# Fan_control_design_v2.net
KiCad netlist of a schematic drawn in EAGLE
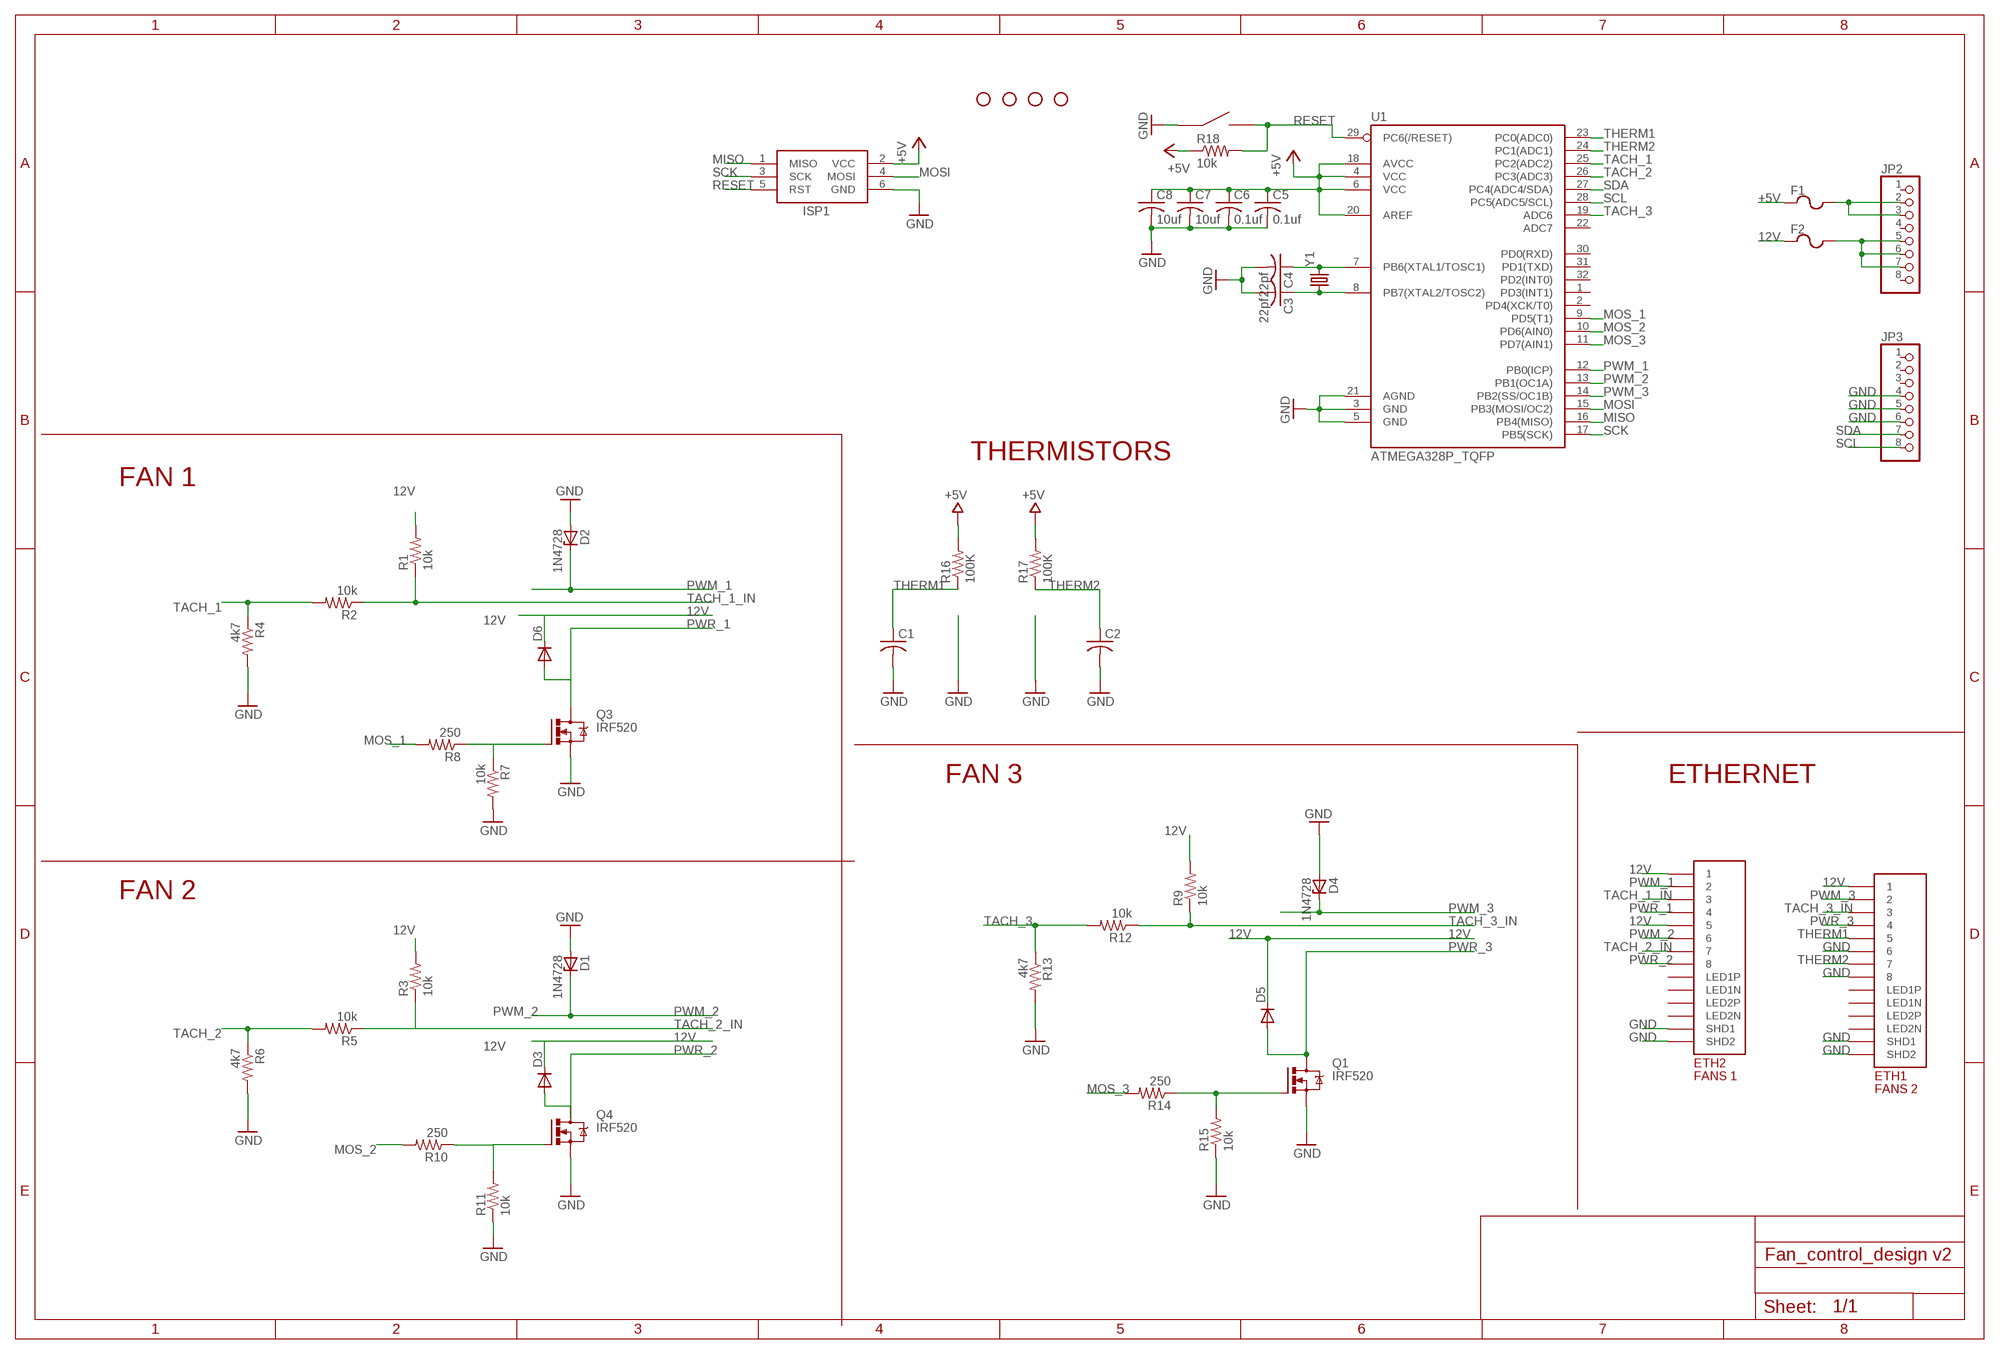
[diagram p0: schematic, sheet 1]

(export (version "E")
  (design (tool "Eeschema 10.0.6"))
  (components
    (comp (ref "C1")
      (value "C-USC0603K")
      (footprint "eagle-import:C0603K")
      (libsource (lib "eagle-import") (part "C-USC0603K"))
    )
    (comp (ref "C2")
      (value "C-USC0603K")
      (footprint "eagle-import:C0603K")
      (libsource (lib "eagle-import") (part "C-USC0603K"))
    )
    (comp (ref "C3")
      (value "22pf")
      (footprint "eagle-import:C0603")
      (libsource (lib "eagle-import") (part "C-USC0603"))
    )
    (comp (ref "C4")
      (value "22pf")
      (footprint "eagle-import:C0603")
      (libsource (lib "eagle-import") (part "C-USC0603"))
    )
    (comp (ref "C5")
      (value "0.1uf")
      (footprint "eagle-import:C0603")
      (libsource (lib "eagle-import") (part "C-USC0603"))
    )
    (comp (ref "C6")
      (value "0.1uf")
      (footprint "eagle-import:C0603")
      (libsource (lib "eagle-import") (part "C-USC0603"))
    )
    (comp (ref "C7")
      (value "10uf")
      (footprint "eagle-import:C0603")
      (libsource (lib "eagle-import") (part "C-USC0603"))
    )
    (comp (ref "C8")
      (value "10uf")
      (footprint "eagle-import:C0603")
      (libsource (lib "eagle-import") (part "C-USC0603"))
    )
    (comp (ref "D1")
      (value "1N4728")
      (footprint "eagle-import:DO41Z10")
      (libsource (lib "eagle-import") (part "1N4728"))
    )
    (comp (ref "D2")
      (value "1N4728")
      (footprint "eagle-import:DO41Z10")
      (libsource (lib "eagle-import") (part "1N4728"))
    )
    (comp (ref "D3")
      (value "DIODE-DO214AC")
      (footprint "eagle-import:DO214AC")
      (libsource (lib "eagle-import") (part "DIODE-DO214AC"))
    )
    (comp (ref "D4")
      (value "1N4728")
      (footprint "eagle-import:DO41Z10")
      (libsource (lib "eagle-import") (part "1N4728"))
    )
    (comp (ref "D5")
      (value "DIODE-DO214AC")
      (footprint "eagle-import:DO214AC")
      (libsource (lib "eagle-import") (part "DIODE-DO214AC"))
    )
    (comp (ref "D6")
      (value "DIODE-DO214AC")
      (footprint "eagle-import:DO214AC")
      (libsource (lib "eagle-import") (part "DIODE-DO214AC"))
    )
    (comp (ref "ETH1")
      (value "FANS 2")
      (footprint "eagle-import:A122645-ND")
      (libsource (lib "eagle-import") (part "ETHERNET"))
    )
    (comp (ref "ETH2")
      (value "FANS 1")
      (footprint "eagle-import:A122645-ND")
      (libsource (lib "eagle-import") (part "ETHERNET"))
    )
    (comp (ref "F1")
      (value "POLYFUSE")
      (footprint "eagle-import:1206")
      (libsource (lib "eagle-import") (part "POLYFUSE"))
    )
    (comp (ref "F2")
      (value "POLYFUSE")
      (footprint "eagle-import:1206")
      (libsource (lib "eagle-import") (part "POLYFUSE"))
    )
    (comp (ref "ISP1")
      (value "AVRISP-BOX")
      (footprint "eagle-import:AVRISP-BOX")
      (libsource (lib "eagle-import") (part "AVRISP-BOX"))
    )
    (comp (ref "JP2")
      (value "PINHD-1X8BIG")
      (footprint "eagle-import:1X08-BIG")
      (libsource (lib "eagle-import") (part "PINHD-1X8BIG"))
    )
    (comp (ref "JP3")
      (value "PINHD-1X8BIG")
      (footprint "eagle-import:1X08-BIG")
      (libsource (lib "eagle-import") (part "PINHD-1X8BIG"))
    )
    (comp (ref "Q1")
      (value "IRF520")
      (footprint "eagle-import:TO220BV")
      (libsource (lib "eagle-import") (part "IRF520"))
    )
    (comp (ref "Q3")
      (value "IRF520")
      (footprint "eagle-import:TO220BV")
      (libsource (lib "eagle-import") (part "IRF520"))
    )
    (comp (ref "Q4")
      (value "IRF520")
      (footprint "eagle-import:TO220BV")
      (libsource (lib "eagle-import") (part "IRF520"))
    )
    (comp (ref "R1")
      (value "10k")
      (footprint "eagle-import:R0603")
      (libsource (lib "eagle-import") (part "R-US_R0603"))
    )
    (comp (ref "R2")
      (value "10k")
      (footprint "eagle-import:R0603")
      (libsource (lib "eagle-import") (part "R-US_R0603"))
    )
    (comp (ref "R3")
      (value "10k")
      (footprint "eagle-import:R0603")
      (libsource (lib "eagle-import") (part "R-US_R0603"))
    )
    (comp (ref "R4")
      (value "4k7")
      (footprint "eagle-import:R0603")
      (libsource (lib "eagle-import") (part "R-US_R0603"))
    )
    (comp (ref "R5")
      (value "10k")
      (footprint "eagle-import:R0603")
      (libsource (lib "eagle-import") (part "R-US_R0603"))
    )
    (comp (ref "R6")
      (value "4k7")
      (footprint "eagle-import:R0603")
      (libsource (lib "eagle-import") (part "R-US_R0603"))
    )
    (comp (ref "R7")
      (value "10k")
      (footprint "eagle-import:R0603")
      (libsource (lib "eagle-import") (part "R-US_R0603"))
    )
    (comp (ref "R8")
      (value "250")
      (footprint "eagle-import:R0603")
      (libsource (lib "eagle-import") (part "R-US_R0603"))
    )
    (comp (ref "R9")
      (value "10k")
      (footprint "eagle-import:R0603")
      (libsource (lib "eagle-import") (part "R-US_R0603"))
    )
    (comp (ref "R10")
      (value "250")
      (footprint "eagle-import:R0603")
      (libsource (lib "eagle-import") (part "R-US_R0603"))
    )
    (comp (ref "R11")
      (value "10k")
      (footprint "eagle-import:R0603")
      (libsource (lib "eagle-import") (part "R-US_R0603"))
    )
    (comp (ref "R12")
      (value "10k")
      (footprint "eagle-import:R0603")
      (libsource (lib "eagle-import") (part "R-US_R0603"))
    )
    (comp (ref "R13")
      (value "4k7")
      (footprint "eagle-import:R0603")
      (libsource (lib "eagle-import") (part "R-US_R0603"))
    )
    (comp (ref "R14")
      (value "250")
      (footprint "eagle-import:R0603")
      (libsource (lib "eagle-import") (part "R-US_R0603"))
    )
    (comp (ref "R15")
      (value "10k")
      (footprint "eagle-import:R0603")
      (libsource (lib "eagle-import") (part "R-US_R0603"))
    )
    (comp (ref "R16")
      (value "100K")
      (footprint "eagle-import:R0603")
      (libsource (lib "eagle-import") (part "R-US_R0603"))
    )
    (comp (ref "R17")
      (value "100K")
      (footprint "eagle-import:R0603")
      (libsource (lib "eagle-import") (part "R-US_R0603"))
    )
    (comp (ref "R18")
      (value "10k")
      (footprint "eagle-import:R0603")
      (libsource (lib "eagle-import") (part "R-US_R0603"))
    )
    (comp (ref "STANDOFF1")
      (value "STAND-OFF")
      (footprint "eagle-import:STAND-OFF")
      (libsource (lib "eagle-import") (part "STAND-OFF"))
    )
    (comp (ref "STANDOFF2")
      (value "STAND-OFF")
      (footprint "eagle-import:STAND-OFF")
      (libsource (lib "eagle-import") (part "STAND-OFF"))
    )
    (comp (ref "STANDOFF3")
      (value "STAND-OFF")
      (footprint "eagle-import:STAND-OFF")
      (libsource (lib "eagle-import") (part "STAND-OFF"))
    )
    (comp (ref "STANDOFF4")
      (value "STAND-OFF")
      (footprint "eagle-import:STAND-OFF")
      (libsource (lib "eagle-import") (part "STAND-OFF"))
    )
    (comp (ref "U$3")
      (value "EG4621CT-ND")
      (footprint "eagle-import:EG4621CT-ND")
      (libsource (lib "eagle-import") (part "EG4621CT-ND"))
    )
    (comp (ref "U1")
      (value "ATMEGA328P_TQFP")
      (footprint "eagle-import:TQFP32-08")
      (libsource (lib "eagle-import") (part "ATMEGA328P_TQFP"))
    )
    (comp (ref "Y1")
      (value "CRYSTALHC49US")
      (footprint "eagle-import:HC49US")
      (libsource (lib "eagle-import") (part "CRYSTALHC49US"))
    )
  )
  (nets
    (net (code "1") (name "+5V") (class "Default")
      (node (ref "C5") (pin "1") (pinfunction "1_1") (pintype "passive"))
      (node (ref "C6") (pin "1") (pinfunction "1_1") (pintype "passive"))
      (node (ref "C7") (pin "1") (pinfunction "1_1") (pintype "passive"))
      (node (ref "C8") (pin "1") (pinfunction "1_1") (pintype "passive"))
      (node (ref "F1") (pin "1") (pinfunction "1_1") (pintype "passive"))
      (node (ref "ISP1") (pin "2") (pinfunction "VCC_2") (pintype "power_in"))
      (node (ref "R16") (pin "2") (pinfunction "2_2") (pintype "passive"))
      (node (ref "R17") (pin "2") (pinfunction "2_2") (pintype "passive"))
      (node (ref "R18") (pin "1") (pinfunction "1_1") (pintype "passive"))
      (node (ref "U1") (pin "18") (pinfunction "AVCC_18") (pintype "bidirectional"))
      (node (ref "U1") (pin "20") (pinfunction "AREF_20") (pintype "bidirectional"))
      (node (ref "U1") (pin "4") (pinfunction "VCC_4") (pintype "bidirectional"))
      (node (ref "U1") (pin "6") (pinfunction "VCC_6") (pintype "bidirectional"))
    )
    (net (code "2") (name "/12V") (class "Default")
      (node (ref "D3") (pin "C") (pinfunction "C_C") (pintype "passive"))
      (node (ref "D5") (pin "C") (pinfunction "C_C") (pintype "passive"))
      (node (ref "D6") (pin "C") (pinfunction "C_C") (pintype "passive"))
      (node (ref "ETH1") (pin "P$1") (pinfunction "1_P$1") (pintype "bidirectional"))
      (node (ref "ETH2") (pin "P$1") (pinfunction "1_P$1") (pintype "bidirectional"))
      (node (ref "ETH2") (pin "P$5") (pinfunction "5_P$5") (pintype "bidirectional"))
      (node (ref "F2") (pin "1") (pinfunction "1_1") (pintype "passive"))
      (node (ref "R1") (pin "2") (pinfunction "2_2") (pintype "passive"))
      (node (ref "R3") (pin "2") (pinfunction "2_2") (pintype "passive"))
      (node (ref "R9") (pin "2") (pinfunction "2_2") (pintype "passive"))
    )
    (net (code "3") (name "/MISO") (class "Default")
      (node (ref "ISP1") (pin "1") (pinfunction "MISO_1") (pintype "input"))
      (node (ref "U1") (pin "16") (pinfunction "PB4(MISO)_16") (pintype "bidirectional"))
    )
    (net (code "4") (name "/MOSI") (class "Default")
      (node (ref "ISP1") (pin "4") (pinfunction "MOSI_4") (pintype "output"))
      (node (ref "U1") (pin "15") (pinfunction "PB3(MOSI/OC2)_15") (pintype "bidirectional"))
    )
    (net (code "5") (name "/MOS_1") (class "Default")
      (node (ref "R8") (pin "2") (pinfunction "2_2") (pintype "passive"))
      (node (ref "U1") (pin "9") (pinfunction "PD5(T1)_9") (pintype "bidirectional"))
    )
    (net (code "6") (name "/MOS_2") (class "Default")
      (node (ref "R10") (pin "2") (pinfunction "2_2") (pintype "passive"))
      (node (ref "U1") (pin "10") (pinfunction "PD6(AIN0)_10") (pintype "bidirectional"))
    )
    (net (code "7") (name "/MOS_3") (class "Default")
      (node (ref "R14") (pin "2") (pinfunction "2_2") (pintype "passive"))
      (node (ref "U1") (pin "11") (pinfunction "PD7(AIN1)_11") (pintype "bidirectional"))
    )
    (net (code "8") (name "/PWM_1") (class "Default")
      (node (ref "D2") (pin "C") (pinfunction "C_C") (pintype "passive"))
      (node (ref "ETH2") (pin "P$2") (pinfunction "2_P$2") (pintype "bidirectional"))
      (node (ref "U1") (pin "12") (pinfunction "PB0(ICP)_12") (pintype "bidirectional"))
    )
    (net (code "9") (name "/PWM_2") (class "Default")
      (node (ref "D1") (pin "C") (pinfunction "C_C") (pintype "passive"))
      (node (ref "ETH2") (pin "P$6") (pinfunction "6_P$6") (pintype "bidirectional"))
      (node (ref "U1") (pin "13") (pinfunction "PB1(OC1A)_13") (pintype "bidirectional"))
    )
    (net (code "10") (name "/PWM_3") (class "Default")
      (node (ref "D4") (pin "C") (pinfunction "C_C") (pintype "passive"))
      (node (ref "ETH1") (pin "P$2") (pinfunction "2_P$2") (pintype "bidirectional"))
      (node (ref "U1") (pin "14") (pinfunction "PB2(SS/OC1B)_14") (pintype "bidirectional"))
    )
    (net (code "11") (name "/PWR_1") (class "Default")
      (node (ref "D6") (pin "A") (pinfunction "A_A") (pintype "passive"))
      (node (ref "ETH2") (pin "P$4") (pinfunction "4_P$4") (pintype "bidirectional"))
      (node (ref "Q3") (pin "D") (pinfunction "D_D") (pintype "passive"))
    )
    (net (code "12") (name "/PWR_2") (class "Default")
      (node (ref "D3") (pin "A") (pinfunction "A_A") (pintype "passive"))
      (node (ref "ETH2") (pin "P$8") (pinfunction "8_P$8") (pintype "bidirectional"))
      (node (ref "Q4") (pin "D") (pinfunction "D_D") (pintype "passive"))
    )
    (net (code "13") (name "/PWR_3") (class "Default")
      (node (ref "D5") (pin "A") (pinfunction "A_A") (pintype "passive"))
      (node (ref "ETH1") (pin "P$4") (pinfunction "4_P$4") (pintype "bidirectional"))
      (node (ref "Q1") (pin "D") (pinfunction "D_D") (pintype "passive"))
    )
    (net (code "14") (name "/RESET") (class "Default")
      (node (ref "ISP1") (pin "5") (pinfunction "RST_5") (pintype "output"))
      (node (ref "R18") (pin "2") (pinfunction "2_2") (pintype "passive"))
      (node (ref "U$3") (pin "P$3") (pinfunction "P$2_P$3") (pintype "bidirectional"))
      (node (ref "U$3") (pin "P$4") (pinfunction "P$2_P$4") (pintype "bidirectional"))
      (node (ref "U1") (pin "29") (pinfunction "PC6(/RESET)_29") (pintype "bidirectional"))
    )
    (net (code "15") (name "/SCK") (class "Default")
      (node (ref "ISP1") (pin "3") (pinfunction "SCK_3") (pintype "output"))
      (node (ref "U1") (pin "17") (pinfunction "PB5(SCK)_17") (pintype "bidirectional"))
    )
    (net (code "16") (name "/SCL") (class "Default")
      (node (ref "JP3") (pin "8") (pinfunction "8_8") (pintype "passive"))
      (node (ref "U1") (pin "28") (pinfunction "PC5(ADC5/SCL)_28") (pintype "bidirectional"))
    )
    (net (code "17") (name "/SDA") (class "Default")
      (node (ref "JP3") (pin "7") (pinfunction "7_7") (pintype "passive"))
      (node (ref "U1") (pin "27") (pinfunction "PC4(ADC4/SDA)_27") (pintype "bidirectional"))
    )
    (net (code "18") (name "/TACH_1") (class "Default")
      (node (ref "R2") (pin "2") (pinfunction "2_2") (pintype "passive"))
      (node (ref "R4") (pin "1") (pinfunction "1_1") (pintype "passive"))
      (node (ref "U1") (pin "25") (pinfunction "PC2(ADC2)_25") (pintype "bidirectional"))
    )
    (net (code "19") (name "/TACH_1_IN") (class "Default")
      (node (ref "ETH2") (pin "P$3") (pinfunction "3_P$3") (pintype "bidirectional"))
      (node (ref "R1") (pin "1") (pinfunction "1_1") (pintype "passive"))
      (node (ref "R2") (pin "1") (pinfunction "1_1") (pintype "passive"))
    )
    (net (code "20") (name "/TACH_2") (class "Default")
      (node (ref "R5") (pin "2") (pinfunction "2_2") (pintype "passive"))
      (node (ref "R6") (pin "1") (pinfunction "1_1") (pintype "passive"))
      (node (ref "U1") (pin "26") (pinfunction "PC3(ADC3)_26") (pintype "bidirectional"))
    )
    (net (code "21") (name "/TACH_2_IN") (class "Default")
      (node (ref "ETH2") (pin "P$7") (pinfunction "7_P$7") (pintype "bidirectional"))
      (node (ref "R3") (pin "1") (pinfunction "1_1") (pintype "passive"))
      (node (ref "R5") (pin "1") (pinfunction "1_1") (pintype "passive"))
    )
    (net (code "22") (name "/TACH_3") (class "Default")
      (node (ref "R12") (pin "2") (pinfunction "2_2") (pintype "passive"))
      (node (ref "R13") (pin "1") (pinfunction "1_1") (pintype "passive"))
      (node (ref "U1") (pin "19") (pinfunction "ADC6_19") (pintype "bidirectional"))
    )
    (net (code "23") (name "/TACH_3_IN") (class "Default")
      (node (ref "ETH1") (pin "P$3") (pinfunction "3_P$3") (pintype "bidirectional"))
      (node (ref "R12") (pin "1") (pinfunction "1_1") (pintype "passive"))
      (node (ref "R9") (pin "1") (pinfunction "1_1") (pintype "passive"))
    )
    (net (code "24") (name "/THERM1") (class "Default")
      (node (ref "C1") (pin "1") (pinfunction "1_1") (pintype "passive"))
      (node (ref "ETH1") (pin "P$5") (pinfunction "5_P$5") (pintype "bidirectional"))
      (node (ref "R16") (pin "1") (pinfunction "1_1") (pintype "passive"))
      (node (ref "U1") (pin "23") (pinfunction "PC0(ADC0)_23") (pintype "bidirectional"))
    )
    (net (code "25") (name "/THERM2") (class "Default")
      (node (ref "C2") (pin "1") (pinfunction "1_1") (pintype "passive"))
      (node (ref "ETH1") (pin "P$7") (pinfunction "7_P$7") (pintype "bidirectional"))
      (node (ref "R17") (pin "1") (pinfunction "1_1") (pintype "passive"))
      (node (ref "U1") (pin "24") (pinfunction "PC1(ADC1)_24") (pintype "bidirectional"))
    )
    (net (code "26") (name "GND") (class "Default")
      (node (ref "C1") (pin "2") (pinfunction "2_2") (pintype "passive"))
      (node (ref "C2") (pin "2") (pinfunction "2_2") (pintype "passive"))
      (node (ref "C3") (pin "2") (pinfunction "2_2") (pintype "passive"))
      (node (ref "C4") (pin "2") (pinfunction "2_2") (pintype "passive"))
      (node (ref "C5") (pin "2") (pinfunction "2_2") (pintype "passive"))
      (node (ref "C6") (pin "2") (pinfunction "2_2") (pintype "passive"))
      (node (ref "C7") (pin "2") (pinfunction "2_2") (pintype "passive"))
      (node (ref "C8") (pin "2") (pinfunction "2_2") (pintype "passive"))
      (node (ref "D1") (pin "A") (pinfunction "A_A") (pintype "passive"))
      (node (ref "D2") (pin "A") (pinfunction "A_A") (pintype "passive"))
      (node (ref "D4") (pin "A") (pinfunction "A_A") (pintype "passive"))
      (node (ref "ETH1") (pin "P$13") (pinfunction "SHD1_P$13") (pintype "bidirectional"))
      (node (ref "ETH1") (pin "P$14") (pinfunction "SHD2_P$14") (pintype "bidirectional"))
      (node (ref "ETH1") (pin "P$6") (pinfunction "6_P$6") (pintype "bidirectional"))
      (node (ref "ETH1") (pin "P$8") (pinfunction "8_P$8") (pintype "bidirectional"))
      (node (ref "ETH2") (pin "P$13") (pinfunction "SHD1_P$13") (pintype "bidirectional"))
      (node (ref "ETH2") (pin "P$14") (pinfunction "SHD2_P$14") (pintype "bidirectional"))
      (node (ref "ISP1") (pin "6") (pinfunction "GND_6") (pintype "power_in"))
      (node (ref "JP3") (pin "4") (pinfunction "4_4") (pintype "passive"))
      (node (ref "JP3") (pin "5") (pinfunction "5_5") (pintype "passive"))
      (node (ref "JP3") (pin "6") (pinfunction "6_6") (pintype "passive"))
      (node (ref "Q1") (pin "S") (pinfunction "S_S") (pintype "passive"))
      (node (ref "Q3") (pin "S") (pinfunction "S_S") (pintype "passive"))
      (node (ref "Q4") (pin "S") (pinfunction "S_S") (pintype "passive"))
      (node (ref "R11") (pin "1") (pinfunction "1_1") (pintype "passive"))
      (node (ref "R13") (pin "2") (pinfunction "2_2") (pintype "passive"))
      (node (ref "R15") (pin "1") (pinfunction "1_1") (pintype "passive"))
      (node (ref "R4") (pin "2") (pinfunction "2_2") (pintype "passive"))
      (node (ref "R6") (pin "2") (pinfunction "2_2") (pintype "passive"))
      (node (ref "R7") (pin "2") (pinfunction "2_2") (pintype "passive"))
      (node (ref "U$3") (pin "P$1") (pinfunction "P$1_P$1") (pintype "bidirectional"))
      (node (ref "U$3") (pin "P$2") (pinfunction "P$1_P$2") (pintype "bidirectional"))
      (node (ref "U1") (pin "21") (pinfunction "AGND_21") (pintype "bidirectional"))
      (node (ref "U1") (pin "3") (pinfunction "GND_3") (pintype "bidirectional"))
      (node (ref "U1") (pin "5") (pinfunction "GND_5") (pintype "bidirectional"))
    )
    (net (code "27") (name "Net-(F1-Pad2)") (class "Default")
      (node (ref "F1") (pin "2") (pinfunction "2_2") (pintype "passive"))
      (node (ref "JP2") (pin "2") (pinfunction "2_2") (pintype "passive"))
      (node (ref "JP2") (pin "3") (pinfunction "3_3") (pintype "passive"))
    )
    (net (code "28") (name "Net-(F2-Pad2)") (class "Default")
      (node (ref "F2") (pin "2") (pinfunction "2_2") (pintype "passive"))
      (node (ref "JP2") (pin "5") (pinfunction "5_5") (pintype "passive"))
      (node (ref "JP2") (pin "6") (pinfunction "6_6") (pintype "passive"))
      (node (ref "JP2") (pin "7") (pinfunction "7_7") (pintype "passive"))
    )
    (net (code "29") (name "Net-(Q1-PadG)") (class "Default")
      (node (ref "Q1") (pin "G") (pinfunction "G_G") (pintype "passive"))
      (node (ref "R14") (pin "1") (pinfunction "1_1") (pintype "passive"))
      (node (ref "R15") (pin "2") (pinfunction "2_2") (pintype "passive"))
    )
    (net (code "30") (name "Net-(Q3-PadG)") (class "Default")
      (node (ref "Q3") (pin "G") (pinfunction "G_G") (pintype "passive"))
      (node (ref "R7") (pin "1") (pinfunction "1_1") (pintype "passive"))
      (node (ref "R8") (pin "1") (pinfunction "1_1") (pintype "passive"))
    )
    (net (code "31") (name "Net-(Q4-PadG)") (class "Default")
      (node (ref "Q4") (pin "G") (pinfunction "G_G") (pintype "passive"))
      (node (ref "R10") (pin "1") (pinfunction "1_1") (pintype "passive"))
      (node (ref "R11") (pin "2") (pinfunction "2_2") (pintype "passive"))
    )
    (net (code "32") (name "Net-(U1-PB6(XTAL1{slash}TOSC1))") (class "Default")
      (node (ref "C4") (pin "1") (pinfunction "1_1") (pintype "passive"))
      (node (ref "U1") (pin "7") (pinfunction "PB6(XTAL1/TOSC1)_7") (pintype "bidirectional"))
      (node (ref "Y1") (pin "2") (pinfunction "2_2") (pintype "passive"))
    )
    (net (code "33") (name "Net-(U1-PB7(XTAL2{slash}TOSC2))") (class "Default")
      (node (ref "C3") (pin "1") (pinfunction "1_1") (pintype "passive"))
      (node (ref "U1") (pin "8") (pinfunction "PB7(XTAL2/TOSC2)_8") (pintype "bidirectional"))
      (node (ref "Y1") (pin "1") (pinfunction "1_1") (pintype "passive"))
    )
    (net (code "34") (name "unconnected-(ETH1-LED1N-PadP$9)") (class "Default")
      (node (ref "ETH1") (pin "P$9") (pinfunction "LED1N_P$9") (pintype "bidirectional"))
    )
    (net (code "35") (name "unconnected-(ETH1-LED1P-PadP$10)") (class "Default")
      (node (ref "ETH1") (pin "P$10") (pinfunction "LED1P_P$10") (pintype "bidirectional"))
    )
    (net (code "36") (name "unconnected-(ETH1-LED2N-PadP$11)") (class "Default")
      (node (ref "ETH1") (pin "P$11") (pinfunction "LED2N_P$11") (pintype "bidirectional"))
    )
    (net (code "37") (name "unconnected-(ETH1-LED2P-PadP$12)") (class "Default")
      (node (ref "ETH1") (pin "P$12") (pinfunction "LED2P_P$12") (pintype "bidirectional"))
    )
    (net (code "38") (name "unconnected-(ETH2-LED1N-PadP$9)") (class "Default")
      (node (ref "ETH2") (pin "P$9") (pinfunction "LED1N_P$9") (pintype "bidirectional"))
    )
    (net (code "39") (name "unconnected-(ETH2-LED1P-PadP$10)") (class "Default")
      (node (ref "ETH2") (pin "P$10") (pinfunction "LED1P_P$10") (pintype "bidirectional"))
    )
    (net (code "40") (name "unconnected-(ETH2-LED2N-PadP$11)") (class "Default")
      (node (ref "ETH2") (pin "P$11") (pinfunction "LED2N_P$11") (pintype "bidirectional"))
    )
    (net (code "41") (name "unconnected-(ETH2-LED2P-PadP$12)") (class "Default")
      (node (ref "ETH2") (pin "P$12") (pinfunction "LED2P_P$12") (pintype "bidirectional"))
    )
    (net (code "42") (name "unconnected-(JP2-Pad1)") (class "Default")
      (node (ref "JP2") (pin "1") (pinfunction "1_1") (pintype "passive"))
    )
    (net (code "43") (name "unconnected-(JP2-Pad4)") (class "Default")
      (node (ref "JP2") (pin "4") (pinfunction "4_4") (pintype "passive"))
    )
    (net (code "44") (name "unconnected-(JP2-Pad8)") (class "Default")
      (node (ref "JP2") (pin "8") (pinfunction "8_8") (pintype "passive"))
    )
    (net (code "45") (name "unconnected-(JP3-Pad1)") (class "Default")
      (node (ref "JP3") (pin "1") (pinfunction "1_1") (pintype "passive"))
    )
    (net (code "46") (name "unconnected-(JP3-Pad2)") (class "Default")
      (node (ref "JP3") (pin "2") (pinfunction "2_2") (pintype "passive"))
    )
    (net (code "47") (name "unconnected-(JP3-Pad3)") (class "Default")
      (node (ref "JP3") (pin "3") (pinfunction "3_3") (pintype "passive"))
    )
    (net (code "48") (name "unconnected-(U1-ADC7-Pad22)") (class "Default")
      (node (ref "U1") (pin "22") (pinfunction "ADC7_22") (pintype "bidirectional"))
    )
    (net (code "49") (name "unconnected-(U1-PD0(RXD)-Pad30)") (class "Default")
      (node (ref "U1") (pin "30") (pinfunction "PD0(RXD)_30") (pintype "bidirectional"))
    )
    (net (code "50") (name "unconnected-(U1-PD1(TXD)-Pad31)") (class "Default")
      (node (ref "U1") (pin "31") (pinfunction "PD1(TXD)_31") (pintype "bidirectional"))
    )
    (net (code "51") (name "unconnected-(U1-PD2(INT0)-Pad32)") (class "Default")
      (node (ref "U1") (pin "32") (pinfunction "PD2(INT0)_32") (pintype "bidirectional"))
    )
    (net (code "52") (name "unconnected-(U1-PD3(INT1)-Pad1)") (class "Default")
      (node (ref "U1") (pin "1") (pinfunction "PD3(INT1)_1") (pintype "bidirectional"))
    )
    (net (code "53") (name "unconnected-(U1-PD4(XCK{slash}T0)-Pad2)") (class "Default")
      (node (ref "U1") (pin "2") (pinfunction "PD4(XCK/T0)_2") (pintype "bidirectional"))
    )
  )
)
